# 5V5_BOOST.net
KiCad netlist of a schematic drawn in Altium Designer
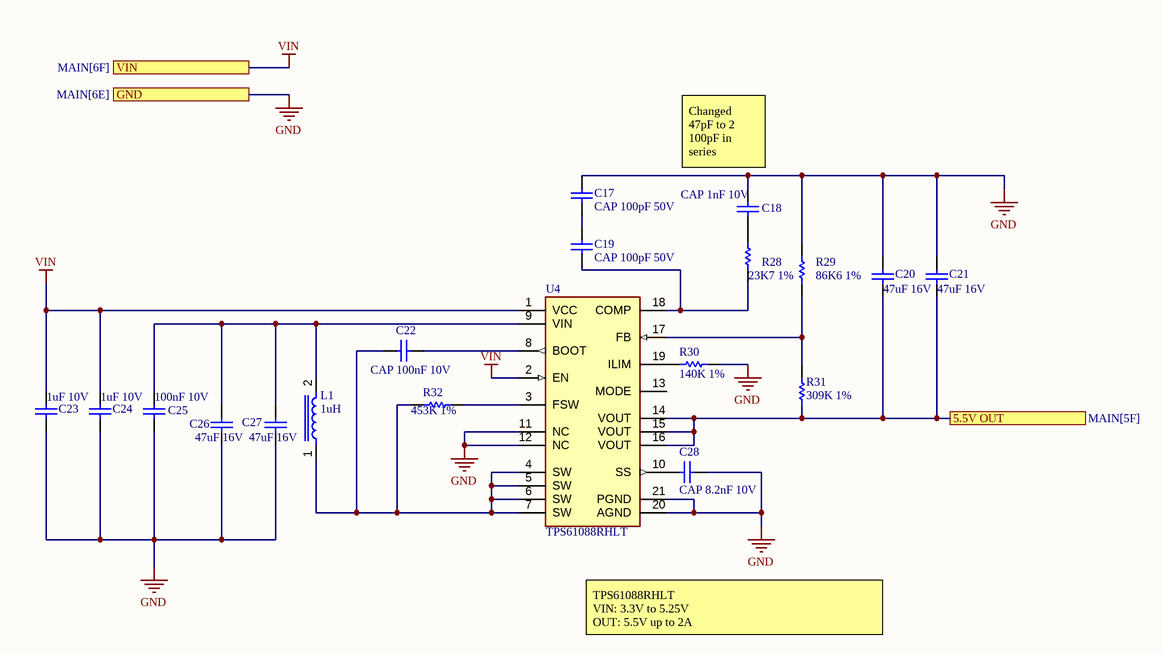
[diagram p0: 5V5_BOOST.SchDoc]

(export (version "E")
  (design (tool "Eeschema 10.0.6"))
  (components
    (comp (ref "C17")
      (value "CAP 100pF 50V")
      (footprint "CAPC0603(1608)100_L")
      (description "CAP 100pF 50V ±20% 0603 (1608 Metric) Thickness 1mm SMD")
      (fields (field (name "TOLERANCE") "Â±20%"))
      (libsource (lib "Altium Content Vault") (part "CAP"))
    )
    (comp (ref "C18")
      (value "CAP 1nF 10V")
      (footprint "CAPC0603(1608)100_M")
      (description "CAP 1nF 10V ±1% 0603 (1608 Metric) Thickness 1mm SMD")
      (fields (field (name "TOLERANCE") "Â±1%"))
      (libsource (lib "Altium Content Vault") (part "CAP"))
    )
    (comp (ref "C19")
      (value "CAP 100pF 50V")
      (footprint "CAPC0603(1608)100_L")
      (description "CAP 100pF 50V ±20% 0603 (1608 Metric) Thickness 1mm SMD")
      (fields (field (name "TOLERANCE") "Â±20%"))
      (libsource (lib "Altium Content Vault") (part "CAP"))
    )
    (comp (ref "C20")
      (value "47uF 16V")
      (footprint "MURA-1210_H_2.7_L")
      (description "Cap Ceramic, 47 uF, +/- 10%, -55 to 85 degC, 2-Pin SMD (1210), RoHS, Tape and Reel")
      (fields (field (name "TOLERANCE") "±10%") (field (name "MANUFACTURER") "Murata"))
      (libsource (lib "Altium Content Vault") (part "CAP-NP-2"))
    )
    (comp (ref "C21")
      (value "47uF 16V")
      (footprint "MURA-1210_H_2.7_L")
      (description "Cap Ceramic, 47 uF, +/- 10%, -55 to 85 degC, 2-Pin SMD (1210), RoHS, Tape and Reel")
      (fields (field (name "TOLERANCE") "±10%") (field (name "MANUFACTURER") "Murata"))
      (libsource (lib "Altium Content Vault") (part "CAP-NP-2"))
    )
    (comp (ref "C22")
      (value "CAP 100nF 10V")
      (footprint "CAPC0603(1608)100_L")
      (description "CAP 100nF 10V ±5% 0603 (1608 Metric) Thickness 1mm SMD")
      (fields (field (name "TOLERANCE") "Â±5%"))
      (libsource (lib "Altium Content Vault") (part "CAP"))
    )
    (comp (ref "C23")
      (value "1uF 10V")
      (footprint "CAPC0603(1608)100_M")
      (description "CAP 1uF 10V ±10% 0603 (1608 Metric) Thickness 1mm SMD")
      (fields (field (name "TOLERANCE") "Â±10%"))
      (libsource (lib "Altium Content Vault") (part "CAP"))
    )
    (comp (ref "C24")
      (value "1uF 10V")
      (footprint "CAPC0603(1608)100_M")
      (description "CAP 1uF 10V ±10% 0603 (1608 Metric) Thickness 1mm SMD")
      (fields (field (name "TOLERANCE") "Â±10%"))
      (libsource (lib "Altium Content Vault") (part "CAP"))
    )
    (comp (ref "C25")
      (value "100nF 10V")
      (footprint "CAPC0603(1608)100_L")
      (description "CAP 100nF 10V ±5% 0603 (1608 Metric) Thickness 1mm SMD")
      (fields (field (name "TOLERANCE") "Â±5%"))
      (libsource (lib "Altium Content Vault") (part "CAP"))
    )
    (comp (ref "C26")
      (value "47uF 16V")
      (footprint "MURA-1210_H_2.7_L")
      (description "Cap Ceramic, 47 uF, +/- 10%, -55 to 85 degC, 2-Pin SMD (1210), RoHS, Tape and Reel")
      (fields (field (name "TOLERANCE") "±10%") (field (name "MANUFACTURER") "Murata"))
      (libsource (lib "Altium Content Vault") (part "CAP-NP-2"))
    )
    (comp (ref "C27")
      (value "47uF 16V")
      (footprint "MURA-1210_H_2.7_L")
      (description "Cap Ceramic, 47 uF, +/- 10%, -55 to 85 degC, 2-Pin SMD (1210), RoHS, Tape and Reel")
      (fields (field (name "TOLERANCE") "±10%") (field (name "MANUFACTURER") "Murata"))
      (libsource (lib "Altium Content Vault") (part "CAP-NP-2"))
    )
    (comp (ref "C28")
      (value "CAP 8.2nF 10V")
      (footprint "CAPC0603(1608)100_N")
      (description "CAP 8.2nF 10V ±5% 0603 (1608 Metric) Thickness 1mm SMD")
      (fields (field (name "TOLERANCE") "Â±5%"))
      (libsource (lib "Altium Content Vault") (part "CAP"))
    )
    (comp (ref "L1")
      (value "1uH")
      (footprint "SRP6540-1R0M")
      (fields
        (field (name "MF") "Bourns")
        (field (name "MP") "SRP6540-1R0M")
        (field (name "TOLERANCE") "20%")
      )
      (libsource (lib "ESE516A2") (part "SRP6540-1R0M"))
    )
    (comp (ref "R28")
      (value "23K7 1%")
      (footprint "RESC0402(1005)_L")
      (description "23K7 0.063W 1% 0402 (1005 Metric)  SMD")
      (fields (field (name "TOLERANCE") "1 %") (field (name "POWER") "0.063 W"))
      (libsource (lib "Altium Content Vault") (part "RES"))
    )
    (comp (ref "R29")
      (value "86K6 1%")
      (footprint "RESC0402(1005)_L")
      (description "86K6 0.063W 1% 0402 (1005 Metric)  SMD")
      (fields (field (name "TOLERANCE") "1 %") (field (name "POWER") "0.063 W"))
      (libsource (lib "Altium Content Vault") (part "RES"))
    )
    (comp (ref "R30")
      (value "140K 1%")
      (footprint "RESC0402(1005)_M")
      (description "140K 0.063W 1% 0402 (1005 Metric)  SMD")
      (fields (field (name "TOLERANCE") "1 %") (field (name "POWER") "0.063 W"))
      (libsource (lib "Altium Content Vault") (part "RES"))
    )
    (comp (ref "R31")
      (value "309K 1%")
      (footprint "RESC0402(1005)_N")
      (description "309K 0.063W 1% 0402 (1005 Metric)  SMD")
      (fields (field (name "TOLERANCE") "1 %") (field (name "POWER") "0.063 W"))
      (libsource (lib "Altium Content Vault") (part "RES"))
    )
    (comp (ref "R32")
      (value "453K 1%")
      (footprint "RESC0402(1005)_L")
      (description "453K 0.063W 1% 0402 (1005 Metric)  SMD")
      (fields (field (name "TOLERANCE") "1 %") (field (name "POWER") "0.063 W"))
      (libsource (lib "Altium Content Vault") (part "RES"))
    )
    (comp (ref "U4")
      (value "TPS61088RHLT")
      (footprint "FP-RHL0020A-MFG")
      (description "IC REG BOOST ADJ 10A 20VQFN")
      (fields
        (field (name "OCTOPART") "https://octopart.com/tps61088rhlt-texas+instruments-57155059")
        (field (name "MANUFACTURER") "Texas Instruments")
      )
      (libsource (lib "Altium Content Vault") (part "866d791168d43c93e8e886550da2fd8"))
    )
  )
  (nets
    (net (code "1") (name "/5.5V OUT") (class "Default")
      (node (ref "C20") (pin "2") (pinfunction "2_2") (pintype "passive"))
      (node (ref "C21") (pin "1") (pinfunction "1_1") (pintype "passive"))
      (node (ref "R31") (pin "1") (pinfunction "1_1") (pintype "passive"))
      (node (ref "U4") (pin "14") (pinfunction "VOUT_14") (pintype "power_in"))
      (node (ref "U4") (pin "15") (pinfunction "VOUT_15") (pintype "power_in"))
      (node (ref "U4") (pin "16") (pinfunction "VOUT_16") (pintype "power_in"))
    )
    (net (code "2") (name "GND") (class "Default")
      (node (ref "C17") (pin "2") (pinfunction "2_2") (pintype "passive"))
      (node (ref "C18") (pin "2") (pinfunction "2_2") (pintype "passive"))
      (node (ref "C20") (pin "1") (pinfunction "1_1") (pintype "passive"))
      (node (ref "C21") (pin "2") (pinfunction "2_2") (pintype "passive"))
      (node (ref "C23") (pin "1") (pinfunction "1_1") (pintype "passive"))
      (node (ref "C24") (pin "1") (pinfunction "1_1") (pintype "passive"))
      (node (ref "C25") (pin "1") (pinfunction "1_1") (pintype "passive"))
      (node (ref "C26") (pin "2") (pinfunction "2_2") (pintype "passive"))
      (node (ref "C27") (pin "1") (pinfunction "1_1") (pintype "passive"))
      (node (ref "C28") (pin "1") (pinfunction "1_1") (pintype "passive"))
      (node (ref "R29") (pin "1") (pinfunction "1_1") (pintype "passive"))
      (node (ref "R30") (pin "2") (pinfunction "2_2") (pintype "passive"))
      (node (ref "U4") (pin "11") (pinfunction "NC_11") (pintype "passive"))
      (node (ref "U4") (pin "12") (pinfunction "NC_12") (pintype "passive"))
      (node (ref "U4") (pin "20") (pinfunction "AGND_20") (pintype "power_in"))
      (node (ref "U4") (pin "21") (pinfunction "PGND_21") (pintype "power_in"))
    )
    (net (code "3") (name "Net-(C17-Pad1)") (class "Default")
      (node (ref "C17") (pin "1") (pinfunction "1_1") (pintype "passive"))
      (node (ref "C19") (pin "2") (pinfunction "2_2") (pintype "passive"))
    )
    (net (code "4") (name "Net-(C18-Pad1)") (class "Default")
      (node (ref "C18") (pin "1") (pinfunction "1_1") (pintype "passive"))
      (node (ref "R28") (pin "2") (pinfunction "2_2") (pintype "passive"))
    )
    (net (code "5") (name "Net-(C22-Pad2)") (class "Default")
      (node (ref "C22") (pin "2") (pinfunction "2_2") (pintype "passive"))
      (node (ref "L1") (pin "1") (pinfunction "1_1") (pintype "passive"))
      (node (ref "R32") (pin "1") (pinfunction "1_1") (pintype "passive"))
      (node (ref "U4") (pin "4") (pinfunction "SW_4") (pintype "power_in"))
      (node (ref "U4") (pin "5") (pinfunction "SW_5") (pintype "power_in"))
      (node (ref "U4") (pin "6") (pinfunction "SW_6") (pintype "power_in"))
      (node (ref "U4") (pin "7") (pinfunction "SW_7") (pintype "power_in"))
    )
    (net (code "6") (name "Net-(U4-BOOT)") (class "Default")
      (node (ref "C22") (pin "1") (pinfunction "1_1") (pintype "passive"))
      (node (ref "U4") (pin "8") (pinfunction "BOOT_8") (pintype "output"))
    )
    (net (code "7") (name "Net-(U4-COMP)") (class "Default")
      (node (ref "C19") (pin "1") (pinfunction "1_1") (pintype "passive"))
      (node (ref "R28") (pin "1") (pinfunction "1_1") (pintype "passive"))
      (node (ref "U4") (pin "18") (pinfunction "COMP_18") (pintype "passive"))
    )
    (net (code "8") (name "Net-(U4-FB)") (class "Default")
      (node (ref "R29") (pin "2") (pinfunction "2_2") (pintype "passive"))
      (node (ref "R31") (pin "2") (pinfunction "2_2") (pintype "passive"))
      (node (ref "U4") (pin "17") (pinfunction "FB_17") (pintype "input"))
    )
    (net (code "9") (name "Net-(U4-FSW)") (class "Default")
      (node (ref "R32") (pin "2") (pinfunction "2_2") (pintype "passive"))
      (node (ref "U4") (pin "3") (pinfunction "FSW_3") (pintype "passive"))
    )
    (net (code "10") (name "Net-(U4-ILIM)") (class "Default")
      (node (ref "R30") (pin "1") (pinfunction "1_1") (pintype "passive"))
      (node (ref "U4") (pin "19") (pinfunction "ILIM_19") (pintype "passive"))
    )
    (net (code "11") (name "Net-(U4-SS)") (class "Default")
      (node (ref "C28") (pin "2") (pinfunction "2_2") (pintype "passive"))
      (node (ref "U4") (pin "10") (pinfunction "SS_10") (pintype "output"))
    )
    (net (code "12") (name "Net-(U4-VIN)") (class "Default")
      (node (ref "C25") (pin "2") (pinfunction "2_2") (pintype "passive"))
      (node (ref "C26") (pin "1") (pinfunction "1_1") (pintype "passive"))
      (node (ref "C27") (pin "2") (pinfunction "2_2") (pintype "passive"))
      (node (ref "L1") (pin "2") (pinfunction "2_2") (pintype "passive"))
      (node (ref "U4") (pin "9") (pinfunction "VIN_9") (pintype "power_in"))
    )
    (net (code "13") (name "VIN") (class "Default")
      (node (ref "C23") (pin "2") (pinfunction "2_2") (pintype "passive"))
      (node (ref "C24") (pin "2") (pinfunction "2_2") (pintype "passive"))
      (node (ref "U4") (pin "1") (pinfunction "VCC_1") (pintype "power_in"))
      (node (ref "U4") (pin "2") (pinfunction "EN_2") (pintype "input"))
    )
    (net (code "14") (name "unconnected-(U4-MODE-Pad13)") (class "Default")
      (node (ref "U4") (pin "13") (pinfunction "MODE_13") (pintype "open_collector"))
    )
  )
)
